# amp-test.net
KiCad netlist of a schematic drawn in EAGLE
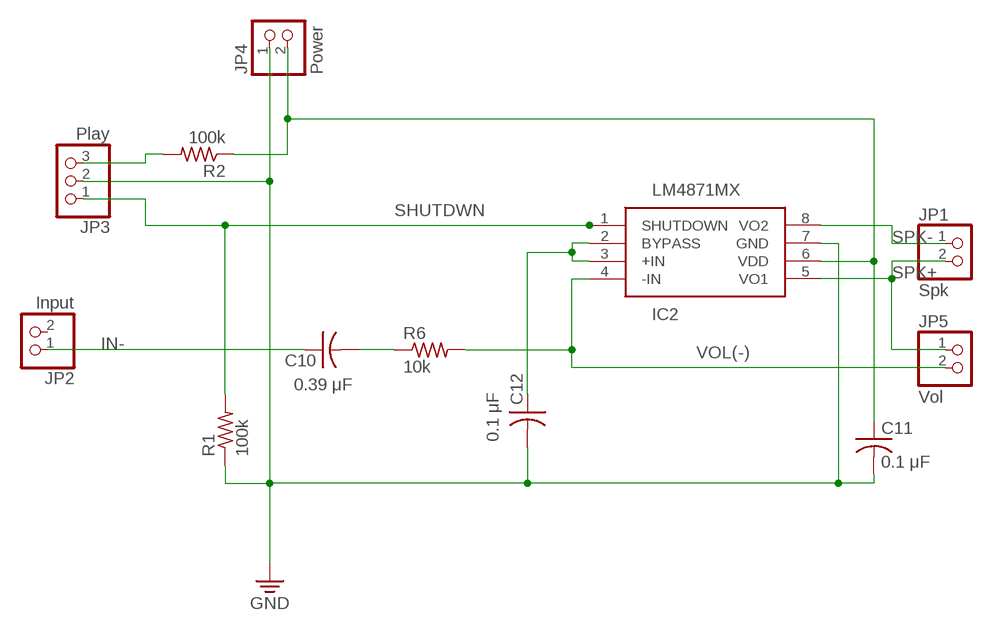
[diagram p0: schematic, sheet 1]

(export (version "E")
  (design (tool "Eeschema 10.0.6"))
  (components
    (comp (ref "C10")
      (value "0.39 μF")
      (footprint "eagle-import:C0805")
      (libsource (lib "eagle-import") (part "C-USC0805"))
    )
    (comp (ref "C11")
      (value "0.1 μF")
      (footprint "eagle-import:C0805")
      (libsource (lib "eagle-import") (part "C-USC0805"))
    )
    (comp (ref "C12")
      (value "0.1 μF")
      (footprint "eagle-import:C0805")
      (libsource (lib "eagle-import") (part "C-USC0805"))
    )
    (comp (ref "IC2")
      (value "LM4871MX")
      (footprint "eagle-import:SOIC127P600X175-8N")
      (fields
        (field (name "MANUFACTURER_PART_NUMBER") "LM4871MX/NOPB")
        (field (name "MOUSER_PART_NUMBER") "926-LM4871MX/NOPB")
      )
      (libsource (lib "eagle-import") (part "LM4871MX_NOPB"))
    )
    (comp (ref "JP1")
      (value "Spk")
      (footprint "eagle-import:1X02")
      (libsource (lib "eagle-import") (part "PINHD-1X2"))
    )
    (comp (ref "JP2")
      (value "Input")
      (footprint "eagle-import:1X02")
      (libsource (lib "eagle-import") (part "PINHD-1X2"))
    )
    (comp (ref "JP3")
      (value "Play")
      (footprint "eagle-import:1X03")
      (libsource (lib "eagle-import") (part "PINHD-1X3"))
    )
    (comp (ref "JP4")
      (value "Power")
      (footprint "eagle-import:1X02")
      (libsource (lib "eagle-import") (part "PINHD-1X2"))
    )
    (comp (ref "JP5")
      (value "Vol")
      (footprint "eagle-import:1X02")
      (libsource (lib "eagle-import") (part "PINHD-1X2"))
    )
    (comp (ref "R1")
      (value "100k")
      (footprint "eagle-import:R0805")
      (libsource (lib "eagle-import") (part "R-US_R0805"))
    )
    (comp (ref "R2")
      (value "100k")
      (footprint "eagle-import:R0805")
      (libsource (lib "eagle-import") (part "R-US_R0805"))
    )
    (comp (ref "R6")
      (value "10k")
      (footprint "eagle-import:R0805")
      (libsource (lib "eagle-import") (part "R-US_R0805"))
    )
  )
  (nets
    (net (code "1") (name "/IN-") (class "Default")
      (node (ref "C10") (pin "1") (pinfunction "1_1") (pintype "passive"))
      (node (ref "JP2") (pin "1") (pinfunction "1_1") (pintype "passive"))
    )
    (net (code "2") (name "/SHUTDWN") (class "Default")
      (node (ref "IC2") (pin "1") (pinfunction "SHUTDOWN_1") (pintype "bidirectional"))
      (node (ref "JP3") (pin "1") (pinfunction "1_1") (pintype "passive"))
      (node (ref "R1") (pin "2") (pinfunction "2_2") (pintype "passive"))
    )
    (net (code "3") (name "/SPK+") (class "Default")
      (node (ref "IC2") (pin "5") (pinfunction "VO1_5") (pintype "bidirectional"))
      (node (ref "JP1") (pin "2") (pinfunction "2_2") (pintype "passive"))
      (node (ref "JP5") (pin "1") (pinfunction "1_1") (pintype "passive"))
    )
    (net (code "4") (name "/SPK-") (class "Default")
      (node (ref "IC2") (pin "8") (pinfunction "VO2_8") (pintype "bidirectional"))
      (node (ref "JP1") (pin "1") (pinfunction "1_1") (pintype "passive"))
    )
    (net (code "5") (name "/VOL(-)") (class "Default")
      (node (ref "IC2") (pin "4") (pinfunction "-IN_4") (pintype "bidirectional"))
      (node (ref "JP5") (pin "2") (pinfunction "2_2") (pintype "passive"))
      (node (ref "R6") (pin "2") (pinfunction "2_2") (pintype "passive"))
    )
    (net (code "6") (name "GND") (class "Default")
      (node (ref "C11") (pin "2") (pinfunction "2_2") (pintype "passive"))
      (node (ref "C12") (pin "2") (pinfunction "2_2") (pintype "passive"))
      (node (ref "IC2") (pin "7") (pinfunction "GND_7") (pintype "bidirectional"))
      (node (ref "JP3") (pin "2") (pinfunction "2_2") (pintype "passive"))
      (node (ref "JP4") (pin "1") (pinfunction "1_1") (pintype "passive"))
      (node (ref "R1") (pin "1") (pinfunction "1_1") (pintype "passive"))
    )
    (net (code "7") (name "Net-(C10-Pad2)") (class "Default")
      (node (ref "C10") (pin "2") (pinfunction "2_2") (pintype "passive"))
      (node (ref "R6") (pin "1") (pinfunction "1_1") (pintype "passive"))
    )
    (net (code "8") (name "Net-(IC2-+IN)") (class "Default")
      (node (ref "C12") (pin "1") (pinfunction "1_1") (pintype "passive"))
      (node (ref "IC2") (pin "2") (pinfunction "BYPASS_2") (pintype "bidirectional"))
      (node (ref "IC2") (pin "3") (pinfunction "+IN_3") (pintype "bidirectional"))
    )
    (net (code "9") (name "Net-(IC2-VDD)") (class "Default")
      (node (ref "C11") (pin "1") (pinfunction "1_1") (pintype "passive"))
      (node (ref "IC2") (pin "6") (pinfunction "VDD_6") (pintype "bidirectional"))
      (node (ref "JP4") (pin "2") (pinfunction "2_2") (pintype "passive"))
      (node (ref "R2") (pin "1") (pinfunction "1_1") (pintype "passive"))
    )
    (net (code "10") (name "Net-(JP3-Pad3)") (class "Default")
      (node (ref "JP3") (pin "3") (pinfunction "3_3") (pintype "passive"))
      (node (ref "R2") (pin "2") (pinfunction "2_2") (pintype "passive"))
    )
    (net (code "11") (name "unconnected-(JP2-Pad2)") (class "Default")
      (node (ref "JP2") (pin "2") (pinfunction "2_2") (pintype "passive"))
    )
  )
)
